# design-1v2.net
KiCad netlist of a schematic drawn in EAGLE
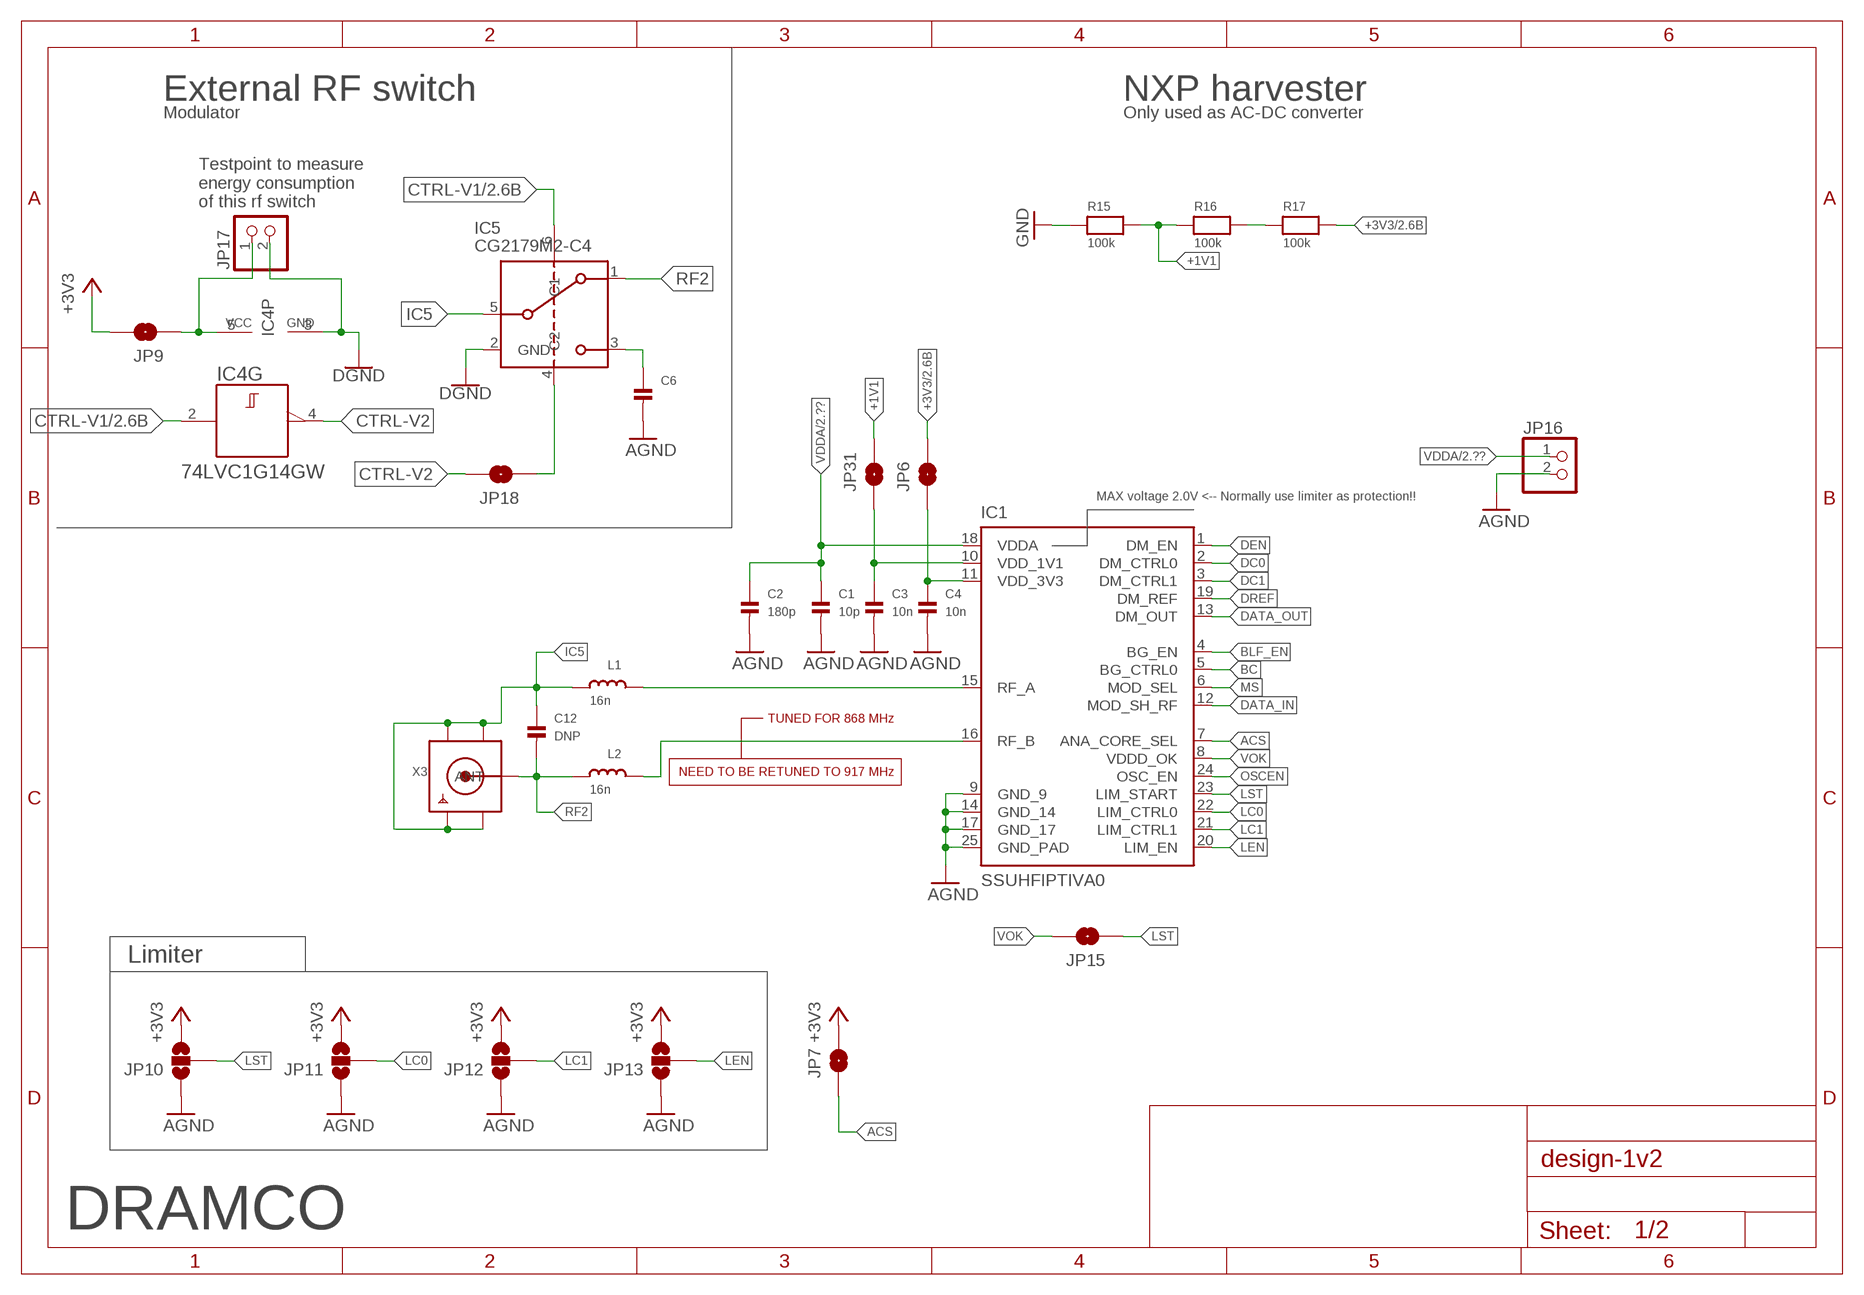
[diagram p0: schematic, sheet 1]
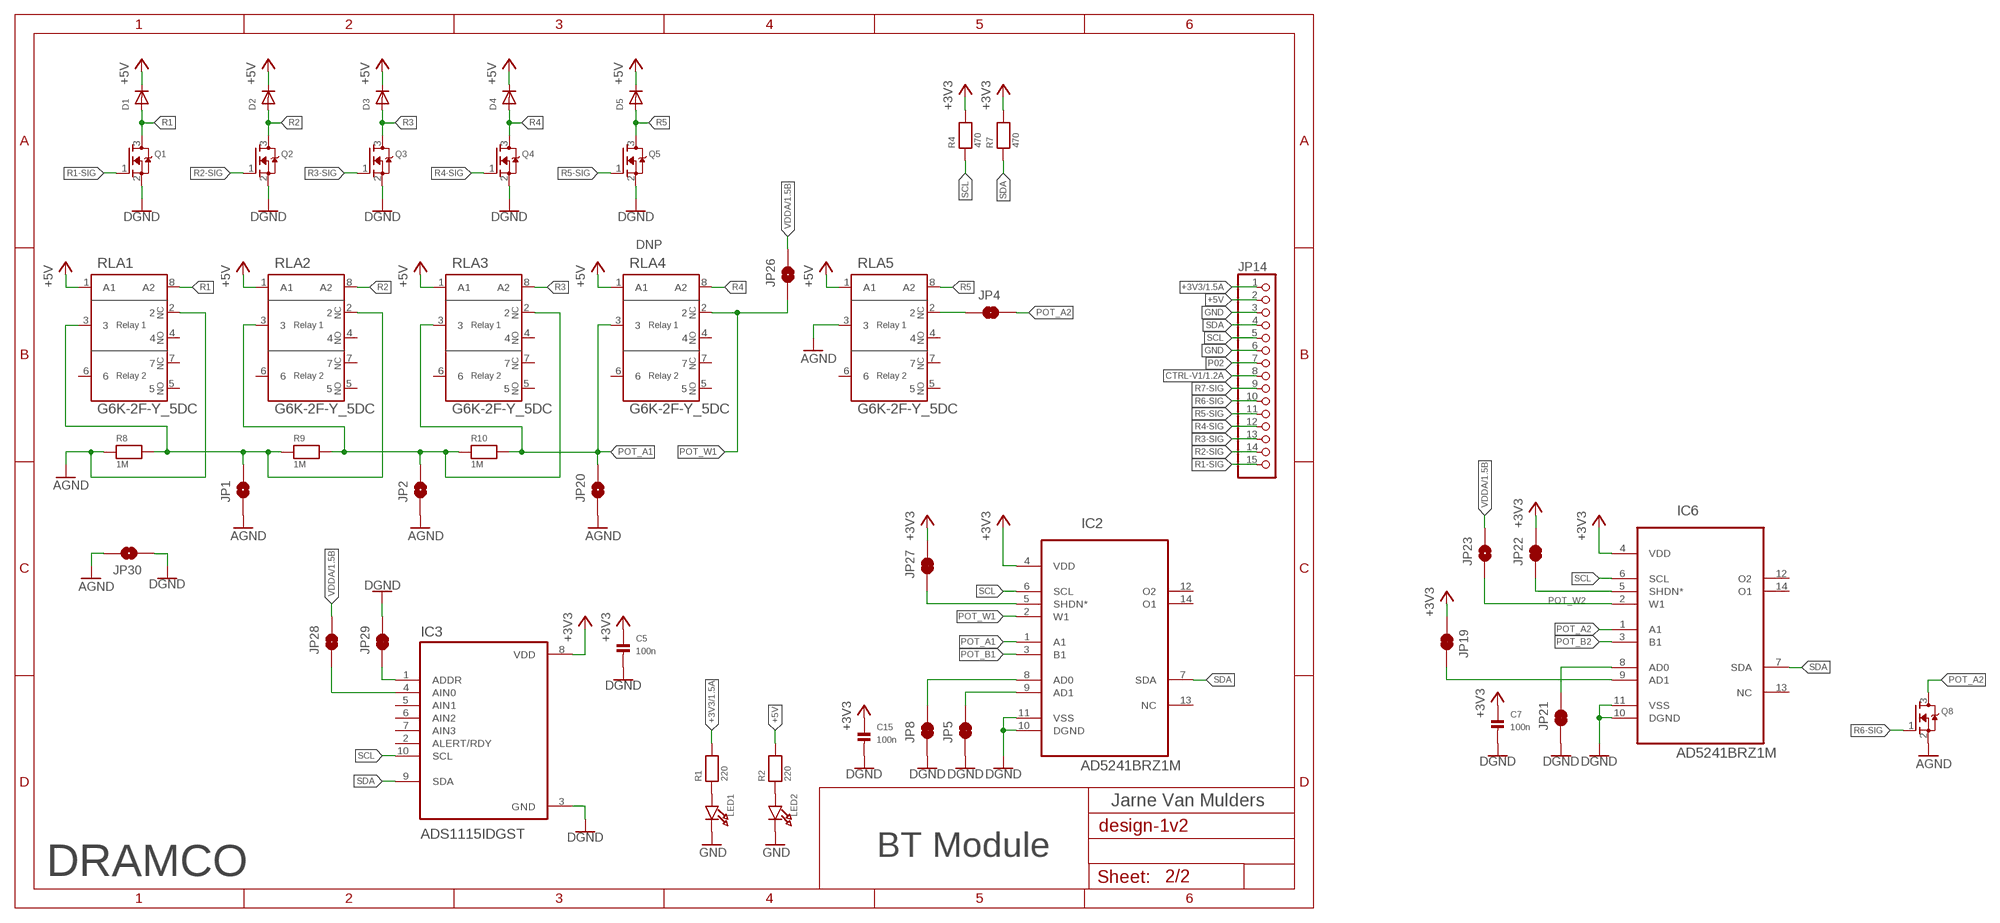
[diagram p1: schematic, sheet 2]

(export (version "E")
  (design (tool "Eeschema 10.0.6"))
  (components
    (comp (ref "C5")
      (value "100n")
      (footprint "eagle-import:0603")
      (libsource (lib "eagle-import") (part "CAP_CERAMIC0603"))
    )
    (comp (ref "C7")
      (value "100n")
      (footprint "eagle-import:0603")
      (libsource (lib "eagle-import") (part "CAP_CERAMIC0603"))
    )
    (comp (ref "C15")
      (value "100n")
      (footprint "eagle-import:0603")
      (libsource (lib "eagle-import") (part "CAP_CERAMIC0603"))
    )
    (comp (ref "D1")
      (value "DIODESOD-123")
      (footprint "eagle-import:SOD-123")
      (libsource (lib "eagle-import") (part "DIODESOD-123"))
    )
    (comp (ref "D2")
      (value "DIODESOD-123")
      (footprint "eagle-import:SOD-123")
      (libsource (lib "eagle-import") (part "DIODESOD-123"))
    )
    (comp (ref "D3")
      (value "DIODESOD-123")
      (footprint "eagle-import:SOD-123")
      (libsource (lib "eagle-import") (part "DIODESOD-123"))
    )
    (comp (ref "D4")
      (value "DIODESOD-123")
      (footprint "eagle-import:SOD-123")
      (libsource (lib "eagle-import") (part "DIODESOD-123"))
    )
    (comp (ref "D5")
      (value "DIODESOD-123")
      (footprint "eagle-import:SOD-123")
      (libsource (lib "eagle-import") (part "DIODESOD-123"))
    )
    (comp (ref "IC2")
      (value "AD5241BRZ1M")
      (footprint "eagle-import:SOIC127P600X175-14N")
      (fields (field (name "MF") "Analog Devices"))
      (libsource (lib "eagle-import") (part "AD5241BRZ1M"))
    )
    (comp (ref "IC3")
      (value "ADS1115IDGST")
      (footprint "eagle-import:SOP50P490X110-10N")
      (fields (field (name "MF") "Texas Instruments"))
      (libsource (lib "eagle-import") (part "ADS1115IDGST"))
    )
    (comp (ref "IC6")
      (value "AD5241BRZ1M")
      (footprint "eagle-import:SOIC127P600X175-14N")
      (fields (field (name "MF") "Analog Devices"))
      (libsource (lib "eagle-import") (part "AD5241BRZ1M"))
    )
    (comp (ref "JP1")
      (value "JUMPER-SMT_2_NO_NO-SILK")
      (footprint "eagle-import:SMT-JUMPER_2_NO_NO-SILK")
      (libsource (lib "eagle-import") (part "JUMPER-SMT_2_NO_NO-SILK"))
    )
    (comp (ref "JP2")
      (value "JUMPER-SMT_2_NO_NO-SILK")
      (footprint "eagle-import:SMT-JUMPER_2_NO_NO-SILK")
      (libsource (lib "eagle-import") (part "JUMPER-SMT_2_NO_NO-SILK"))
    )
    (comp (ref "JP4")
      (value "JUMPER-SMT_2_NO_NO-SILK")
      (footprint "eagle-import:SMT-JUMPER_2_NO_NO-SILK")
      (libsource (lib "eagle-import") (part "JUMPER-SMT_2_NO_NO-SILK"))
    )
    (comp (ref "JP5")
      (value "JUMPER-SMT_2_NC_TRACE_NO-SILK")
      (footprint "eagle-import:SMT-JUMPER_2_NC_TRACE_NO-SILK")
      (libsource (lib "eagle-import") (part "JUMPER-SMT_2_NC_TRACE_NO-SILK"))
    )
    (comp (ref "JP8")
      (value "JUMPER-SMT_2_NC_TRACE_NO-SILK")
      (footprint "eagle-import:SMT-JUMPER_2_NC_TRACE_NO-SILK")
      (libsource (lib "eagle-import") (part "JUMPER-SMT_2_NC_TRACE_NO-SILK"))
    )
    (comp (ref "JP14")
      (value "HEADER-1X15")
      (footprint "eagle-import:1X15_ROUND_70")
      (libsource (lib "eagle-import") (part "HEADER-1X15"))
    )
    (comp (ref "JP19")
      (value "JUMPER-SMT_2_NC_TRACE_NO-SILK")
      (footprint "eagle-import:SMT-JUMPER_2_NC_TRACE_NO-SILK")
      (libsource (lib "eagle-import") (part "JUMPER-SMT_2_NC_TRACE_NO-SILK"))
    )
    (comp (ref "JP20")
      (value "JUMPER-SMT_2_NO_NO-SILK")
      (footprint "eagle-import:SMT-JUMPER_2_NO_NO-SILK")
      (libsource (lib "eagle-import") (part "JUMPER-SMT_2_NO_NO-SILK"))
    )
    (comp (ref "JP21")
      (value "JUMPER-SMT_2_NC_TRACE_NO-SILK")
      (footprint "eagle-import:SMT-JUMPER_2_NC_TRACE_NO-SILK")
      (libsource (lib "eagle-import") (part "JUMPER-SMT_2_NC_TRACE_NO-SILK"))
    )
    (comp (ref "JP22")
      (value "JUMPER-SMT_2_NC_TRACE_NO-SILK")
      (footprint "eagle-import:SMT-JUMPER_2_NC_TRACE_NO-SILK")
      (libsource (lib "eagle-import") (part "JUMPER-SMT_2_NC_TRACE_NO-SILK"))
    )
    (comp (ref "JP23")
      (value "JUMPER-SMT_2_NO_NO-SILK")
      (footprint "eagle-import:SMT-JUMPER_2_NO_NO-SILK")
      (libsource (lib "eagle-import") (part "JUMPER-SMT_2_NO_NO-SILK"))
    )
    (comp (ref "JP26")
      (value "JUMPER-SMT_2_NO_NO-SILK")
      (footprint "eagle-import:SMT-JUMPER_2_NO_NO-SILK")
      (libsource (lib "eagle-import") (part "JUMPER-SMT_2_NO_NO-SILK"))
    )
    (comp (ref "JP27")
      (value "JUMPER-SMT_2_NC_TRACE_NO-SILK")
      (footprint "eagle-import:SMT-JUMPER_2_NC_TRACE_NO-SILK")
      (libsource (lib "eagle-import") (part "JUMPER-SMT_2_NC_TRACE_NO-SILK"))
    )
    (comp (ref "JP28")
      (value "JUMPER-SMT_2_NO_NO-SILK")
      (footprint "eagle-import:SMT-JUMPER_2_NO_NO-SILK")
      (libsource (lib "eagle-import") (part "JUMPER-SMT_2_NO_NO-SILK"))
    )
    (comp (ref "JP29")
      (value "JUMPER-SMT_2_NC_TRACE_NO-SILK")
      (footprint "eagle-import:SMT-JUMPER_2_NC_TRACE_NO-SILK")
      (libsource (lib "eagle-import") (part "JUMPER-SMT_2_NC_TRACE_NO-SILK"))
    )
    (comp (ref "JP30")
      (value "JUMPER-SMT_2_NO_NO-SILK")
      (footprint "eagle-import:SMT-JUMPER_2_NO_NO-SILK")
      (libsource (lib "eagle-import") (part "JUMPER-SMT_2_NO_NO-SILK"))
    )
    (comp (ref "LED1")
      (value "LED0805")
      (footprint "eagle-import:CHIPLED_0805")
      (libsource (lib "eagle-import") (part "LED0805"))
    )
    (comp (ref "LED2")
      (value "LED0805")
      (footprint "eagle-import:CHIPLED_0805")
      (libsource (lib "eagle-import") (part "LED0805"))
    )
    (comp (ref "Q1")
      (value "MOSFET-NREFLOW")
      (footprint "eagle-import:SOT23-R")
      (libsource (lib "eagle-import") (part "MOSFET-NREFLOW"))
    )
    (comp (ref "Q2")
      (value "MOSFET-NREFLOW")
      (footprint "eagle-import:SOT23-R")
      (libsource (lib "eagle-import") (part "MOSFET-NREFLOW"))
    )
    (comp (ref "Q3")
      (value "MOSFET-NREFLOW")
      (footprint "eagle-import:SOT23-R")
      (libsource (lib "eagle-import") (part "MOSFET-NREFLOW"))
    )
    (comp (ref "Q4")
      (value "MOSFET-NREFLOW")
      (footprint "eagle-import:SOT23-R")
      (libsource (lib "eagle-import") (part "MOSFET-NREFLOW"))
    )
    (comp (ref "Q5")
      (value "MOSFET-NREFLOW")
      (footprint "eagle-import:SOT23-R")
      (libsource (lib "eagle-import") (part "MOSFET-NREFLOW"))
    )
    (comp (ref "Q8")
      (value "MOSFET-NREFLOW")
      (footprint "eagle-import:SOT23-R")
      (libsource (lib "eagle-import") (part "MOSFET-NREFLOW"))
    )
    (comp (ref "R1")
      (value "220")
      (footprint "eagle-import:0603")
      (libsource (lib "eagle-import") (part "RESISTOR0603"))
    )
    (comp (ref "R2")
      (value "220")
      (footprint "eagle-import:0603")
      (libsource (lib "eagle-import") (part "RESISTOR0603"))
    )
    (comp (ref "R4")
      (value "470")
      (footprint "eagle-import:0603")
      (libsource (lib "eagle-import") (part "RESISTOR0603"))
    )
    (comp (ref "R7")
      (value "470")
      (footprint "eagle-import:0603")
      (libsource (lib "eagle-import") (part "RESISTOR0603"))
    )
    (comp (ref "R8")
      (value "1M")
      (footprint "eagle-import:0805")
      (libsource (lib "eagle-import") (part "RESISTOR0805"))
    )
    (comp (ref "R9")
      (value "1M")
      (footprint "eagle-import:0805")
      (libsource (lib "eagle-import") (part "RESISTOR0805"))
    )
    (comp (ref "R10")
      (value "1M")
      (footprint "eagle-import:0805")
      (libsource (lib "eagle-import") (part "RESISTOR0805"))
    )
    (comp (ref "RLA1")
      (value "G6K-2F-Y_5DC")
      (footprint "eagle-import:RELAY_G6K-2F_OMR")
      (fields
        (field (name "MANUFACTURER_PART_NUMBER") "G6K-2F-Y 5DC")
        (field (name "COPYRIGHT") "Copyright (C) 2024 Ultra Librarian. All rights reserved.")
      )
      (libsource (lib "eagle-import") (part "G6K-2F-Y_5DC"))
    )
    (comp (ref "RLA2")
      (value "G6K-2F-Y_5DC")
      (footprint "eagle-import:RELAY_G6K-2F_OMR")
      (fields
        (field (name "MANUFACTURER_PART_NUMBER") "G6K-2F-Y 5DC")
        (field (name "COPYRIGHT") "Copyright (C) 2024 Ultra Librarian. All rights reserved.")
      )
      (libsource (lib "eagle-import") (part "G6K-2F-Y_5DC"))
    )
    (comp (ref "RLA3")
      (value "G6K-2F-Y_5DC")
      (footprint "eagle-import:RELAY_G6K-2F_OMR")
      (fields
        (field (name "MANUFACTURER_PART_NUMBER") "G6K-2F-Y 5DC")
        (field (name "COPYRIGHT") "Copyright (C) 2024 Ultra Librarian. All rights reserved.")
      )
      (libsource (lib "eagle-import") (part "G6K-2F-Y_5DC"))
    )
    (comp (ref "RLA4")
      (value "G6K-2F-Y_5DC")
      (footprint "eagle-import:RELAY_G6K-2F_OMR")
      (fields
        (field (name "MANUFACTURER_PART_NUMBER") "G6K-2F-Y 5DC")
        (field (name "COPYRIGHT") "Copyright (C) 2024 Ultra Librarian. All rights reserved.")
      )
      (libsource (lib "eagle-import") (part "G6K-2F-Y_5DC"))
    )
    (comp (ref "RLA5")
      (value "G6K-2F-Y_5DC")
      (footprint "eagle-import:RELAY_G6K-2F_OMR")
      (fields
        (field (name "MANUFACTURER_PART_NUMBER") "G6K-2F-Y 5DC")
        (field (name "COPYRIGHT") "Copyright (C) 2024 Ultra Librarian. All rights reserved.")
      )
      (libsource (lib "eagle-import") (part "G6K-2F-Y_5DC"))
    )
    (comp (ref "C1")
      (value "10p")
      (footprint "eagle-import:0603")
      (libsource (lib "eagle-import") (part "CAP_CERAMIC0603"))
    )
    (comp (ref "C2")
      (value "180p")
      (footprint "eagle-import:0603")
      (libsource (lib "eagle-import") (part "CAP_CERAMIC0603"))
    )
    (comp (ref "C3")
      (value "10n")
      (footprint "eagle-import:0603")
      (libsource (lib "eagle-import") (part "CAP_CERAMIC0603"))
    )
    (comp (ref "C4")
      (value "10n")
      (footprint "eagle-import:0603")
      (libsource (lib "eagle-import") (part "CAP_CERAMIC0603"))
    )
    (comp (ref "C6")
      (value "CAP_CERAMIC0402")
      (footprint "eagle-import:0402")
      (libsource (lib "eagle-import") (part "CAP_CERAMIC0402"))
    )
    (comp (ref "C12")
      (value "DNP")
      (footprint "eagle-import:0402")
      (libsource (lib "eagle-import") (part "CAP_CERAMIC0402"))
    )
    (comp (ref "IC1")
      (value "SSUHFIPTIVA0")
      (footprint "eagle-import:QFN50P400X400X90-25N")
      (libsource (lib "eagle-import") (part "SSUHFIPTIVA0"))
    )
    (comp (ref "IC4")
      (value "74LVC1G14GW")
      (footprint "eagle-import:SOT353-1")
      (libsource (lib "eagle-import") (part "74LVC1G14GW"))
    )
    (comp (ref "IC5")
      (value "CG2179M2-C4")
      (footprint "eagle-import:SC70-6-CNC04")
      (fields (field (name "MF") "CEL"))
      (libsource (lib "eagle-import") (part "CG2179M2-C4"))
    )
    (comp (ref "JP6")
      (value "JUMPER-SMT_2_NO_NO-SILK")
      (footprint "eagle-import:SMT-JUMPER_2_NO_NO-SILK")
      (libsource (lib "eagle-import") (part "JUMPER-SMT_2_NO_NO-SILK"))
    )
    (comp (ref "JP7")
      (value "JUMPER-SMT_2_NO_NO-SILK")
      (footprint "eagle-import:SMT-JUMPER_2_NO_NO-SILK")
      (libsource (lib "eagle-import") (part "JUMPER-SMT_2_NO_NO-SILK"))
    )
    (comp (ref "JP9")
      (value "JUMPER-SMT_2_NO_NO-SILK")
      (footprint "eagle-import:SMT-JUMPER_2_NO_NO-SILK")
      (libsource (lib "eagle-import") (part "JUMPER-SMT_2_NO_NO-SILK"))
    )
    (comp (ref "JP10")
      (value "JUMPER-SMT_3_NO_SILK")
      (footprint "eagle-import:SMT-JUMPER_3_NO_SILK")
      (libsource (lib "eagle-import") (part "JUMPER-SMT_3_NO_SILK"))
    )
    (comp (ref "JP11")
      (value "JUMPER-SMT_3_NO_SILK")
      (footprint "eagle-import:SMT-JUMPER_3_NO_SILK")
      (libsource (lib "eagle-import") (part "JUMPER-SMT_3_NO_SILK"))
    )
    (comp (ref "JP12")
      (value "JUMPER-SMT_3_NO_SILK")
      (footprint "eagle-import:SMT-JUMPER_3_NO_SILK")
      (libsource (lib "eagle-import") (part "JUMPER-SMT_3_NO_SILK"))
    )
    (comp (ref "JP13")
      (value "JUMPER-SMT_3_NO_SILK")
      (footprint "eagle-import:SMT-JUMPER_3_NO_SILK")
      (libsource (lib "eagle-import") (part "JUMPER-SMT_3_NO_SILK"))
    )
    (comp (ref "JP15")
      (value "JUMPER-SMT_2_NO_NO-SILK")
      (footprint "eagle-import:SMT-JUMPER_2_NO_NO-SILK")
      (libsource (lib "eagle-import") (part "JUMPER-SMT_2_NO_NO-SILK"))
    )
    (comp (ref "JP16")
      (value "HEADER-1X2ROUND")
      (footprint "eagle-import:1X02_ROUND")
      (libsource (lib "eagle-import") (part "HEADER-1X2ROUND"))
    )
    (comp (ref "JP17")
      (value "HEADER-1X2ROUND")
      (footprint "eagle-import:1X02_ROUND")
      (libsource (lib "eagle-import") (part "HEADER-1X2ROUND"))
    )
    (comp (ref "JP18")
      (value "JUMPER-SMT_2_NO_NO-SILK")
      (footprint "eagle-import:SMT-JUMPER_2_NO_NO-SILK")
      (libsource (lib "eagle-import") (part "JUMPER-SMT_2_NO_NO-SILK"))
    )
    (comp (ref "JP31")
      (value "JUMPER-SMT_2_NO_NO-SILK")
      (footprint "eagle-import:SMT-JUMPER_2_NO_NO-SILK")
      (libsource (lib "eagle-import") (part "JUMPER-SMT_2_NO_NO-SILK"))
    )
    (comp (ref "L1")
      (value "16n")
      (footprint "eagle-import:_0402")
      (libsource (lib "eagle-import") (part "INDUCTOR_0402"))
    )
    (comp (ref "L2")
      (value "16n")
      (footprint "eagle-import:_0402")
      (libsource (lib "eagle-import") (part "INDUCTOR_0402"))
    )
    (comp (ref "R15")
      (value "100k")
      (footprint "eagle-import:0603")
      (libsource (lib "eagle-import") (part "RESISTOR0603"))
    )
    (comp (ref "R16")
      (value "100k")
      (footprint "eagle-import:0603")
      (libsource (lib "eagle-import") (part "RESISTOR0603"))
    )
    (comp (ref "R17")
      (value "100k")
      (footprint "eagle-import:0603")
      (libsource (lib "eagle-import") (part "RESISTOR0603"))
    )
    (comp (ref "X3")
      (value "SMACONNECTOR_EDGE_UFL")
      (footprint "eagle-import:SMA_EDGELAUNCH_UFL")
      (libsource (lib "eagle-import") (part "SMACONNECTOR_EDGE_UFL"))
    )
  )
  (nets
    (net (code "1") (name "+1V1") (class "Default")
      (node (ref "JP31") (pin "2") (pinfunction "2_2") (pintype "passive"))
      (node (ref "R15") (pin "2") (pinfunction "2_2") (pintype "passive"))
      (node (ref "R16") (pin "1") (pinfunction "1_1") (pintype "passive"))
    )
    (net (code "2") (name "+3V3") (class "Default")
      (node (ref "C15") (pin "1") (pinfunction "P$1_1") (pintype "passive"))
      (node (ref "C5") (pin "1") (pinfunction "P$1_1") (pintype "passive"))
      (node (ref "C7") (pin "1") (pinfunction "P$1_1") (pintype "passive"))
      (node (ref "IC2") (pin "4") (pinfunction "VDD_4") (pintype "power_in"))
      (node (ref "IC3") (pin "8") (pinfunction "VDD_8") (pintype "power_in"))
      (node (ref "IC6") (pin "4") (pinfunction "VDD_4") (pintype "power_in"))
      (node (ref "JP10") (pin "3") (pinfunction "3_3") (pintype "passive"))
      (node (ref "JP11") (pin "3") (pinfunction "3_3") (pintype "passive"))
      (node (ref "JP12") (pin "3") (pinfunction "3_3") (pintype "passive"))
      (node (ref "JP13") (pin "3") (pinfunction "3_3") (pintype "passive"))
      (node (ref "JP14") (pin "1") (pinfunction "1_1") (pintype "passive"))
      (node (ref "JP19") (pin "1") (pinfunction "1_1") (pintype "passive"))
      (node (ref "JP22") (pin "2") (pinfunction "2_2") (pintype "passive"))
      (node (ref "JP27") (pin "2") (pinfunction "2_2") (pintype "passive"))
      (node (ref "JP6") (pin "2") (pinfunction "2_2") (pintype "passive"))
      (node (ref "JP7") (pin "2") (pinfunction "2_2") (pintype "passive"))
      (node (ref "JP9") (pin "2") (pinfunction "2_2") (pintype "passive"))
      (node (ref "R1") (pin "2") (pinfunction "2_2") (pintype "passive"))
      (node (ref "R17") (pin "2") (pinfunction "2_2") (pintype "passive"))
      (node (ref "R4") (pin "2") (pinfunction "2_2") (pintype "passive"))
      (node (ref "R7") (pin "2") (pinfunction "2_2") (pintype "passive"))
    )
    (net (code "3") (name "+5V") (class "Default")
      (node (ref "D1") (pin "C") (pinfunction "C_C") (pintype "passive"))
      (node (ref "D2") (pin "C") (pinfunction "C_C") (pintype "passive"))
      (node (ref "D3") (pin "C") (pinfunction "C_C") (pintype "passive"))
      (node (ref "D4") (pin "C") (pinfunction "C_C") (pintype "passive"))
      (node (ref "D5") (pin "C") (pinfunction "C_C") (pintype "passive"))
      (node (ref "JP14") (pin "2") (pinfunction "2_2") (pintype "passive"))
      (node (ref "R2") (pin "2") (pinfunction "2_2") (pintype "passive"))
      (node (ref "RLA1") (pin "1") (pinfunction "A1_1") (pintype "passive"))
      (node (ref "RLA2") (pin "1") (pinfunction "A1_1") (pintype "passive"))
      (node (ref "RLA3") (pin "1") (pinfunction "A1_1") (pintype "passive"))
      (node (ref "RLA4") (pin "1") (pinfunction "A1_1") (pintype "passive"))
      (node (ref "RLA5") (pin "1") (pinfunction "A1_1") (pintype "passive"))
    )
    (net (code "4") (name "ACS") (class "Default")
      (node (ref "IC1") (pin "7") (pinfunction "ANA_CORE_SEL_7") (pintype "bidirectional"))
      (node (ref "JP7") (pin "1") (pinfunction "1_1") (pintype "passive"))
    )
    (net (code "5") (name "AGND") (class "Default")
      (node (ref "C1") (pin "2") (pinfunction "P$2_2") (pintype "passive"))
      (node (ref "C2") (pin "2") (pinfunction "P$2_2") (pintype "passive"))
      (node (ref "C3") (pin "2") (pinfunction "P$2_2") (pintype "passive"))
      (node (ref "C4") (pin "2") (pinfunction "P$2_2") (pintype "passive"))
      (node (ref "C6") (pin "2") (pinfunction "P$2_2") (pintype "passive"))
      (node (ref "IC1") (pin "14") (pinfunction "GND_14_14") (pintype "bidirectional"))
      (node (ref "IC1") (pin "17") (pinfunction "GND_17_17") (pintype "bidirectional"))
      (node (ref "IC1") (pin "25") (pinfunction "GND_PAD_25") (pintype "bidirectional"))
      (node (ref "IC1") (pin "9") (pinfunction "GND_9_9") (pintype "bidirectional"))
      (node (ref "JP1") (pin "1") (pinfunction "1_1") (pintype "passive"))
      (node (ref "JP10") (pin "1") (pinfunction "1_1") (pintype "passive"))
      (node (ref "JP11") (pin "1") (pinfunction "1_1") (pintype "passive"))
      (node (ref "JP12") (pin "1") (pinfunction "1_1") (pintype "passive"))
      (node (ref "JP13") (pin "1") (pinfunction "1_1") (pintype "passive"))
      (node (ref "JP16") (pin "2") (pinfunction "2_2") (pintype "passive"))
      (node (ref "JP2") (pin "1") (pinfunction "1_1") (pintype "passive"))
      (node (ref "JP20") (pin "1") (pinfunction "1_1") (pintype "passive"))
      (node (ref "JP30") (pin "2") (pinfunction "2_2") (pintype "passive"))
      (node (ref "Q8") (pin "2") (pinfunction "S_2") (pintype "bidirectional"))
      (node (ref "R8") (pin "1") (pinfunction "1_1") (pintype "passive"))
      (node (ref "RLA1") (pin "2") (pinfunction "2_2") (pintype "passive"))
      (node (ref "RLA5") (pin "3") (pinfunction "3_3") (pintype "passive"))
    )
    (net (code "6") (name "BC") (class "Default")
      (node (ref "IC1") (pin "5") (pinfunction "BG_CTRL0_5") (pintype "bidirectional"))
    )
    (net (code "7") (name "BLF_EN") (class "Default")
      (node (ref "IC1") (pin "4") (pinfunction "BG_EN_4") (pintype "bidirectional"))
    )
    (net (code "8") (name "CTRL-V1") (class "Default")
      (node (ref "IC4") (pin "2") (pinfunction "A_2") (pintype "input"))
      (node (ref "IC5") (pin "6") (pinfunction "C1_6") (pintype "bidirectional"))
      (node (ref "JP14") (pin "8") (pinfunction "8_8") (pintype "passive"))
    )
    (net (code "9") (name "CTRL-V2") (class "Default")
      (node (ref "IC4") (pin "4") (pinfunction "Y_4") (pintype "output"))
      (node (ref "JP18") (pin "2") (pinfunction "2_2") (pintype "passive"))
    )
    (net (code "10") (name "DATA_IN") (class "Default")
      (node (ref "IC1") (pin "12") (pinfunction "MOD_SH_RF_12") (pintype "bidirectional"))
    )
    (net (code "11") (name "DATA_OUT") (class "Default")
      (node (ref "IC1") (pin "13") (pinfunction "DM_OUT_13") (pintype "bidirectional"))
    )
    (net (code "12") (name "DC0") (class "Default")
      (node (ref "IC1") (pin "2") (pinfunction "DM_CTRL0_2") (pintype "bidirectional"))
    )
    (net (code "13") (name "DC1") (class "Default")
      (node (ref "IC1") (pin "3") (pinfunction "DM_CTRL1_3") (pintype "bidirectional"))
    )
    (net (code "14") (name "DEN") (class "Default")
      (node (ref "IC1") (pin "1") (pinfunction "DM_EN_1") (pintype "bidirectional"))
    )
    (net (code "15") (name "DREF") (class "Default")
      (node (ref "IC1") (pin "19") (pinfunction "DM_REF_19") (pintype "bidirectional"))
    )
    (net (code "16") (name "GND") (class "Default")
      (node (ref "C15") (pin "2") (pinfunction "P$2_2") (pintype "passive"))
      (node (ref "C5") (pin "2") (pinfunction "P$2_2") (pintype "passive"))
      (node (ref "C7") (pin "2") (pinfunction "P$2_2") (pintype "passive"))
      (node (ref "IC2") (pin "10") (pinfunction "DGND_10") (pintype "passive"))
      (node (ref "IC2") (pin "11") (pinfunction "VSS_11") (pintype "power_in"))
      (node (ref "IC3") (pin "3") (pinfunction "GND_3") (pintype "power_in"))
      (node (ref "IC4") (pin "3") (pinfunction "GND_3") (pintype "power_in"))
      (node (ref "IC5") (pin "2") (pinfunction "GND_2") (pintype "bidirectional"))
      (node (ref "IC6") (pin "10") (pinfunction "DGND_10") (pintype "passive"))
      (node (ref "IC6") (pin "11") (pinfunction "VSS_11") (pintype "power_in"))
      (node (ref "JP14") (pin "3") (pinfunction "3_3") (pintype "passive"))
      (node (ref "JP14") (pin "6") (pinfunction "6_6") (pintype "passive"))
      (node (ref "JP17") (pin "2") (pinfunction "2_2") (pintype "passive"))
      (node (ref "JP21") (pin "1") (pinfunction "1_1") (pintype "passive"))
      (node (ref "JP29") (pin "2") (pinfunction "2_2") (pintype "passive"))
      (node (ref "JP30") (pin "1") (pinfunction "1_1") (pintype "passive"))
      (node (ref "JP5") (pin "1") (pinfunction "1_1") (pintype "passive"))
      (node (ref "JP8") (pin "1") (pinfunction "1_1") (pintype "passive"))
      (node (ref "LED1") (pin "C") (pinfunction "C_C") (pintype "passive"))
      (node (ref "LED2") (pin "C") (pinfunction "C_C") (pintype "passive"))
      (node (ref "Q1") (pin "2") (pinfunction "S_2") (pintype "bidirectional"))
      (node (ref "Q2") (pin "2") (pinfunction "S_2") (pintype "bidirectional"))
      (node (ref "Q3") (pin "2") (pinfunction "S_2") (pintype "bidirectional"))
      (node (ref "Q4") (pin "2") (pinfunction "S_2") (pintype "bidirectional"))
      (node (ref "Q5") (pin "2") (pinfunction "S_2") (pintype "bidirectional"))
      (node (ref "R15") (pin "1") (pinfunction "1_1") (pintype "passive"))
    )
    (net (code "17") (name "IC5") (class "Default")
      (node (ref "C12") (pin "1") (pinfunction "P$1_1") (pintype "passive"))
      (node (ref "IC5") (pin "5") (pinfunction "PC_5") (pintype "bidirectional"))
      (node (ref "L1") (pin "1") (pinfunction "1_1") (pintype "passive"))
      (node (ref "X3") (pin "GND@1") (pinfunction "GND1_GND@1") (pintype "power_in"))
      (node (ref "X3") (pin "GND@2") (pinfunction "GND2_GND@2") (pintype "power_in"))
      (node (ref "X3") (pin "GND@3") (pinfunction "GND3_GND@3") (pintype "power_in"))
      (node (ref "X3") (pin "GND@4") (pinfunction "GND4_GND@4") (pintype "power_in"))
    )
    (net (code "18") (name "LC0") (class "Default")
      (node (ref "IC1") (pin "22") (pinfunction "LIM_CTRL0_22") (pintype "bidirectional"))
      (node (ref "JP11") (pin "2") (pinfunction "2_2") (pintype "passive"))
    )
    (net (code "19") (name "LC1") (class "Default")
      (node (ref "IC1") (pin "21") (pinfunction "LIM_CTRL1_21") (pintype "bidirectional"))
      (node (ref "JP12") (pin "2") (pinfunction "2_2") (pintype "passive"))
    )
    (net (code "20") (name "LEN") (class "Default")
      (node (ref "IC1") (pin "20") (pinfunction "LIM_EN_20") (pintype "bidirectional"))
      (node (ref "JP13") (pin "2") (pinfunction "2_2") (pintype "passive"))
    )
    (net (code "21") (name "LST") (class "Default")
      (node (ref "IC1") (pin "23") (pinfunction "LIM_START_23") (pintype "bidirectional"))
      (node (ref "JP10") (pin "2") (pinfunction "2_2") (pintype "passive"))
      (node (ref "JP15") (pin "1") (pinfunction "1_1") (pintype "passive"))
    )
    (net (code "22") (name "MS") (class "Default")
      (node (ref "IC1") (pin "6") (pinfunction "MOD_SEL_6") (pintype "bidirectional"))
    )
    (net (code "23") (name "Net-(C3-P$1)") (class "Default")
      (node (ref "C3") (pin "1") (pinfunction "P$1_1") (pintype "passive"))
      (node (ref "IC1") (pin "10") (pinfunction "VDD_1V1_10") (pintype "bidirectional"))
      (node (ref "JP31") (pin "1") (pinfunction "1_1") (pintype "passive"))
    )
    (net (code "24") (name "Net-(C4-P$1)") (class "Default")
      (node (ref "C4") (pin "1") (pinfunction "P$1_1") (pintype "passive"))
      (node (ref "IC1") (pin "11") (pinfunction "VDD_3V3_11") (pintype "bidirectional"))
      (node (ref "JP6") (pin "1") (pinfunction "1_1") (pintype "passive"))
    )
    (net (code "25") (name "Net-(C6-P$1)") (class "Default")
      (node (ref "C6") (pin "1") (pinfunction "P$1_1") (pintype "passive"))
      (node (ref "IC5") (pin "3") (pinfunction "P2_3") (pintype "bidirectional"))
    )
    (net (code "26") (name "Net-(IC1-RF_A)") (class "Default")
      (node (ref "IC1") (pin "15") (pinfunction "RF_A_15") (pintype "bidirectional"))
      (node (ref "L1") (pin "2") (pinfunction "2_2") (pintype "passive"))
    )
    (net (code "27") (name "Net-(IC1-RF_B)") (class "Default")
      (node (ref "IC1") (pin "16") (pinfunction "RF_B_16") (pintype "bidirectional"))
      (node (ref "L2") (pin "2") (pinfunction "2_2") (pintype "passive"))
    )
    (net (code "28") (name "Net-(IC2-AD0)") (class "Default")
      (node (ref "IC2") (pin "8") (pinfunction "AD0_8") (pintype "passive"))
      (node (ref "JP8") (pin "2") (pinfunction "2_2") (pintype "passive"))
    )
    (net (code "29") (name "Net-(IC2-AD1)") (class "Default")
      (node (ref "IC2") (pin "9") (pinfunction "AD1_9") (pintype "passive"))
      (node (ref "JP5") (pin "2") (pinfunction "2_2") (pintype "passive"))
    )
    (net (code "30") (name "Net-(IC2-SHDN*)") (class "Default")
      (node (ref "IC2") (pin "5") (pinfunction "SHDN*_5") (pintype "passive"))
      (node (ref "JP27") (pin "1") (pinfunction "1_1") (pintype "passive"))
    )
    (net (code "31") (name "Net-(IC3-ADDR)") (class "Default")
      (node (ref "IC3") (pin "1") (pinfunction "ADDR_1") (pintype "input"))
      (node (ref "JP29") (pin "1") (pinfunction "1_1") (pintype "passive"))
    )
    (net (code "32") (name "Net-(IC3-AIN0)") (class "Default")
      (node (ref "IC3") (pin "4") (pinfunction "AIN0_4") (pintype "input"))
      (node (ref "JP28") (pin "1") (pinfunction "1_1") (pintype "passive"))
    )
    (net (code "33") (name "Net-(IC4B-VCC)") (class "Default")
      (node (ref "IC4") (pin "5") (pinfunction "VCC_5") (pintype "power_in"))
      (node (ref "JP17") (pin "1") (pinfunction "1_1") (pintype "passive"))
      (node (ref "JP9") (pin "1") (pinfunction "1_1") (pintype "passive"))
    )
    (net (code "34") (name "Net-(IC5-C2)") (class "Default")
      (node (ref "IC5") (pin "4") (pinfunction "C2_4") (pintype "bidirectional"))
      (node (ref "JP18") (pin "1") (pinfunction "1_1") (pintype "passive"))
    )
    (net (code "35") (name "Net-(IC6-AD0)") (class "Default")
      (node (ref "IC6") (pin "8") (pinfunction "AD0_8") (pintype "passive"))
      (node (ref "JP21") (pin "2") (pinfunction "2_2") (pintype "passive"))
    )
    (net (code "36") (name "Net-(IC6-AD1)") (class "Default")
      (node (ref "IC6") (pin "9") (pinfunction "AD1_9") (pintype "passive"))
      (node (ref "JP19") (pin "2") (pinfunction "2_2") (pintype "passive"))
    )
    (net (code "37") (name "Net-(IC6-SHDN*)") (class "Default")
      (node (ref "IC6") (pin "5") (pinfunction "SHDN*_5") (pintype "passive"))
      (node (ref "JP22") (pin "1") (pinfunction "1_1") (pintype "passive"))
    )
    (net (code "38") (name "Net-(JP1-Pad2)") (class "Default")
      (node (ref "JP1") (pin "2") (pinfunction "2_2") (pintype "passive"))
      (node (ref "R8") (pin "2") (pinfunction "2_2") (pintype "passive"))
      (node (ref "R9") (pin "1") (pinfunction "1_1") (pintype "passive"))
      (node (ref "RLA1") (pin "3") (pinfunction "3_3") (pintype "passive"))
      (node (ref "RLA2") (pin "2") (pinfunction "2_2") (pintype "passive"))
    )
    (net (code "39") (name "Net-(JP2-Pad2)") (class "Default")
      (node (ref "JP2") (pin "2") (pinfunction "2_2") (pintype "passive"))
      (node (ref "R10") (pin "1") (pinfunction "1_1") (pintype "passive"))
      (node (ref "R9") (pin "2") (pinfunction "2_2") (pintype "passive"))
      (node (ref "RLA2") (pin "3") (pinfunction "3_3") (pintype "passive"))
      (node (ref "RLA3") (pin "2") (pinfunction "2_2") (pintype "passive"))
    )
    (net (code "40") (name "Net-(JP4-Pad1)") (class "Default")
      (node (ref "JP4") (pin "1") (pinfunction "1_1") (pintype "passive"))
      (node (ref "RLA5") (pin "2") (pinfunction "2_2") (pintype "passive"))
    )
    (net (code "41") (name "Net-(LED1-PadA)") (class "Default")
      (node (ref "LED1") (pin "A") (pinfunction "A_A") (pintype "passive"))
      (node (ref "R1") (pin "1") (pinfunction "1_1") (pintype "passive"))
    )
    (net (code "42") (name "Net-(LED2-PadA)") (class "Default")
      (node (ref "LED2") (pin "A") (pinfunction "A_A") (pintype "passive"))
      (node (ref "R2") (pin "1") (pinfunction "1_1") (pintype "passive"))
    )
    (net (code "43") (name "Net-(R16-Pad2)") (class "Default")
      (node (ref "R16") (pin "2") (pinfunction "2_2") (pintype "passive"))
      (node (ref "R17") (pin "1") (pinfunction "1_1") (pintype "passive"))
    )
    (net (code "44") (name "OSCEN") (class "Default")
      (node (ref "IC1") (pin "24") (pinfunction "OSC_EN_24") (pintype "bidirectional"))
    )
    (net (code "45") (name "P02") (class "Default")
      (node (ref "JP14") (pin "7") (pinfunction "7_7") (pintype "passive"))
    )
    (net (code "46") (name "POT_A1") (class "Default")
      (node (ref "IC2") (pin "1") (pinfunction "A1_1") (pintype "passive"))
      (node (ref "JP20") (pin "2") (pinfunction "2_2") (pintype "passive"))
      (node (ref "R10") (pin "2") (pinfunction "2_2") (pintype "passive"))
      (node (ref "RLA3") (pin "3") (pinfunction "3_3") (pintype "passive"))
      (node (ref "RLA4") (pin "3") (pinfunction "3_3") (pintype "passive"))
    )
    (net (code "47") (name "POT_A2") (class "Default")
      (node (ref "IC6") (pin "1") (pinfunction "A1_1") (pintype "passive"))
      (node (ref "JP4") (pin "2") (pinfunction "2_2") (pintype "passive"))
      (node (ref "Q8") (pin "3") (pinfunction "D_3") (pintype "bidirectional"))
    )
    (net (code "48") (name "POT_B1") (class "Default")
      (node (ref "IC2") (pin "3") (pinfunction "B1_3") (pintype "passive"))
    )
    (net (code "49") (name "POT_B2") (class "Default")
      (node (ref "IC6") (pin "3") (pinfunction "B1_3") (pintype "passive"))
    )
    (net (code "50") (name "POT_W1") (class "Default")
      (node (ref "IC2") (pin "2") (pinfunction "W1_2") (pintype "passive"))
      (node (ref "JP26") (pin "1") (pinfunction "1_1") (pintype "passive"))
      (node (ref "RLA4") (pin "2") (pinfunction "2_2") (pintype "passive"))
    )
    (net (code "51") (name "POT_W2") (class "Default")
      (node (ref "IC6") (pin "2") (pinfunction "W1_2") (pintype "passive"))
      (node (ref "JP23") (pin "1") (pinfunction "1_1") (pintype "passive"))
    )
    (net (code "52") (name "R1") (class "Default")
      (node (ref "D1") (pin "A") (pinfunction "A_A") (pintype "passive"))
      (node (ref "Q1") (pin "3") (pinfunction "D_3") (pintype "bidirectional"))
      (node (ref "RLA1") (pin "8") (pinfunction "A2_8") (pintype "passive"))
    )
    (net (code "53") (name "R1-SIG") (class "Default")
      (node (ref "JP14") (pin "15") (pinfunction "15_15") (pintype "passive"))
      (node (ref "Q1") (pin "1") (pinfunction "G_1") (pintype "bidirectional"))
    )
    (net (code "54") (name "R2") (class "Default")
      (node (ref "D2") (pin "A") (pinfunction "A_A") (pintype "passive"))
      (node (ref "Q2") (pin "3") (pinfunction "D_3") (pintype "bidirectional"))
      (node (ref "RLA2") (pin "8") (pinfunction "A2_8") (pintype "passive"))
    )
    (net (code "55") (name "R2-SIG") (class "Default")
      (node (ref "JP14") (pin "14") (pinfunction "14_14") (pintype "passive"))
      (node (ref "Q2") (pin "1") (pinfunction "G_1") (pintype "bidirectional"))
    )
    (net (code "56") (name "R3") (class "Default")
      (node (ref "D3") (pin "A") (pinfunction "A_A") (pintype "passive"))
      (node (ref "Q3") (pin "3") (pinfunction "D_3") (pintype "bidirectional"))
      (node (ref "RLA3") (pin "8") (pinfunction "A2_8") (pintype "passive"))
    )
    (net (code "57") (name "R3-SIG") (class "Default")
      (node (ref "JP14") (pin "13") (pinfunction "13_13") (pintype "passive"))
      (node (ref "Q3") (pin "1") (pinfunction "G_1") (pintype "bidirectional"))
    )
    (net (code "58") (name "R4") (class "Default")
      (node (ref "D4") (pin "A") (pinfunction "A_A") (pintype "passive"))
      (node (ref "Q4") (pin "3") (pinfunction "D_3") (pintype "bidirectional"))
      (node (ref "RLA4") (pin "8") (pinfunction "A2_8") (pintype "passive"))
    )
    (net (code "59") (name "R4-SIG") (class "Default")
      (node (ref "JP14") (pin "12") (pinfunction "12_12") (pintype "passive"))
      (node (ref "Q4") (pin "1") (pinfunction "G_1") (pintype "bidirectional"))
    )
    (net (code "60") (name "R5") (class "Default")
      (node (ref "D5") (pin "A") (pinfunction "A_A") (pintype "passive"))
      (node (ref "Q5") (pin "3") (pinfunction "D_3") (pintype "bidirectional"))
      (node (ref "RLA5") (pin "8") (pinfunction "A2_8") (pintype "passive"))
    )
    (net (code "61") (name "R5-SIG") (class "Default")
      (node (ref "JP14") (pin "11") (pinfunction "11_11") (pintype "passive"))
      (node (ref "Q5") (pin "1") (pinfunction "G_1") (pintype "bidirectional"))
    )
    (net (code "62") (name "R6-SIG") (class "Default")
      (node (ref "JP14") (pin "10") (pinfunction "10_10") (pintype "passive"))
      (node (ref "Q8") (pin "1") (pinfunction "G_1") (pintype "bidirectional"))
    )
    (net (code "63") (name "R7-SIG") (class "Default")
      (node (ref "JP14") (pin "9") (pinfunction "9_9") (pintype "passive"))
    )
    (net (code "64") (name "RF2") (class "Default")
      (node (ref "C12") (pin "2") (pinfunction "P$2_2") (pintype "passive"))
      (node (ref "IC5") (pin "1") (pinfunction "P1_1") (pintype "bidirectional"))
      (node (ref "L2") (pin "1") (pinfunction "1_1") (pintype "passive"))
      (node (ref "X3") (pin "P") (pinfunction "ANT_P") (pintype "bidirectional"))
    )
    (net (code "65") (name "SCL") (class "Default")
      (node (ref "IC2") (pin "6") (pinfunction "SCL_6") (pintype "passive"))
      (node (ref "IC3") (pin "10") (pinfunction "SCL_10") (pintype "input"))
      (node (ref "IC6") (pin "6") (pinfunction "SCL_6") (pintype "passive"))
      (node (ref "JP14") (pin "5") (pinfunction "5_5") (pintype "passive"))
      (node (ref "R4") (pin "1") (pinfunction "1_1") (pintype "passive"))
    )
    (net (code "66") (name "SDA") (class "Default")
      (node (ref "IC2") (pin "7") (pinfunction "SDA_7") (pintype "passive"))
      (node (ref "IC3") (pin "9") (pinfunction "SDA_9") (pintype "bidirectional"))
      (node (ref "IC6") (pin "7") (pinfunction "SDA_7") (pintype "passive"))
      (node (ref "JP14") (pin "4") (pinfunction "4_4") (pintype "passive"))
      (node (ref "R7") (pin "1") (pinfunction "1_1") (pintype "passive"))
    )
    (net (code "67") (name "VDDA") (class "Default")
      (node (ref "C1") (pin "1") (pinfunction "P$1_1") (pintype "passive"))
      (node (ref "C2") (pin "1") (pinfunction "P$1_1") (pintype "passive"))
      (node (ref "IC1") (pin "18") (pinfunction "VDDA_18") (pintype "bidirectional"))
      (node (ref "JP16") (pin "1") (pinfunction "1_1") (pintype "passive"))
      (node (ref "JP23") (pin "2") (pinfunction "2_2") (pintype "passive"))
      (node (ref "JP26") (pin "2") (pinfunction "2_2") (pintype "passive"))
      (node (ref "JP28") (pin "2") (pinfunction "2_2") (pintype "passive"))
    )
    (net (code "68") (name "VOK") (class "Default")
      (node (ref "IC1") (pin "8") (pinfunction "VDDD_OK_8") (pintype "bidirectional"))
      (node (ref "JP15") (pin "2") (pinfunction "2_2") (pintype "passive"))
    )
    (net (code "69") (name "unconnected-(IC2-NC-Pad13)") (class "Default")
      (node (ref "IC2") (pin "13") (pinfunction "NC_13") (pintype "passive"))
    )
    (net (code "70") (name "unconnected-(IC2-O1-Pad14)") (class "Default")
      (node (ref "IC2") (pin "14") (pinfunction "O1_14") (pintype "passive"))
    )
    (net (code "71") (name "unconnected-(IC2-O2-Pad12)") (class "Default")
      (node (ref "IC2") (pin "12") (pinfunction "O2_12") (pintype "passive"))
    )
    (net (code "72") (name "unconnected-(IC3-AIN1-Pad5)") (class "Default")
      (node (ref "IC3") (pin "5") (pinfunction "AIN1_5") (pintype "input"))
    )
    (net (code "73") (name "unconnected-(IC3-AIN2-Pad6)") (class "Default")
      (node (ref "IC3") (pin "6") (pinfunction "AIN2_6") (pintype "input"))
    )
    (net (code "74") (name "unconnected-(IC3-AIN3-Pad7)") (class "Default")
      (node (ref "IC3") (pin "7") (pinfunction "AIN3_7") (pintype "input"))
    )
    (net (code "75") (name "unconnected-(IC3-ALERT{slash}RDY-Pad2)") (class "Default")
      (node (ref "IC3") (pin "2") (pinfunction "ALERT/RDY_2") (pintype "input"))
    )
    (net (code "76") (name "unconnected-(IC6-NC-Pad13)") (class "Default")
      (node (ref "IC6") (pin "13") (pinfunction "NC_13") (pintype "passive"))
    )
    (net (code "77") (name "unconnected-(IC6-O1-Pad14)") (class "Default")
      (node (ref "IC6") (pin "14") (pinfunction "O1_14") (pintype "passive"))
    )
    (net (code "78") (name "unconnected-(IC6-O2-Pad12)") (class "Default")
      (node (ref "IC6") (pin "12") (pinfunction "O2_12") (pintype "passive"))
    )
    (net (code "79") (name "unconnected-(RLA1-Pad4)") (class "Default")
      (node (ref "RLA1") (pin "4") (pinfunction "4_4") (pintype "passive"))
    )
    (net (code "80") (name "unconnected-(RLA1-Pad5)") (class "Default")
      (node (ref "RLA1") (pin "5") (pinfunction "5_5") (pintype "passive"))
    )
    (net (code "81") (name "unconnected-(RLA1-Pad6)") (class "Default")
      (node (ref "RLA1") (pin "6") (pinfunction "6_6") (pintype "passive"))
    )
    (net (code "82") (name "unconnected-(RLA1-Pad7)") (class "Default")
      (node (ref "RLA1") (pin "7") (pinfunction "7_7") (pintype "passive"))
    )
    (net (code "83") (name "unconnected-(RLA2-Pad4)") (class "Default")
      (node (ref "RLA2") (pin "4") (pinfunction "4_4") (pintype "passive"))
    )
    (net (code "84") (name "unconnected-(RLA2-Pad5)") (class "Default")
      (node (ref "RLA2") (pin "5") (pinfunction "5_5") (pintype "passive"))
    )
    (net (code "85") (name "unconnected-(RLA2-Pad6)") (class "Default")
      (node (ref "RLA2") (pin "6") (pinfunction "6_6") (pintype "passive"))
    )
    (net (code "86") (name "unconnected-(RLA2-Pad7)") (class "Default")
      (node (ref "RLA2") (pin "7") (pinfunction "7_7") (pintype "passive"))
    )
    (net (code "87") (name "unconnected-(RLA3-Pad4)") (class "Default")
      (node (ref "RLA3") (pin "4") (pinfunction "4_4") (pintype "passive"))
    )
    (net (code "88") (name "unconnected-(RLA3-Pad5)") (class "Default")
      (node (ref "RLA3") (pin "5") (pinfunction "5_5") (pintype "passive"))
    )
    (net (code "89") (name "unconnected-(RLA3-Pad6)") (class "Default")
      (node (ref "RLA3") (pin "6") (pinfunction "6_6") (pintype "passive"))
    )
    (net (code "90") (name "unconnected-(RLA3-Pad7)") (class "Default")
      (node (ref "RLA3") (pin "7") (pinfunction "7_7") (pintype "passive"))
    )
    (net (code "91") (name "unconnected-(RLA4-Pad4)") (class "Default")
      (node (ref "RLA4") (pin "4") (pinfunction "4_4") (pintype "passive"))
    )
    (net (code "92") (name "unconnected-(RLA4-Pad5)") (class "Default")
      (node (ref "RLA4") (pin "5") (pinfunction "5_5") (pintype "passive"))
    )
    (net (code "93") (name "unconnected-(RLA4-Pad6)") (class "Default")
      (node (ref "RLA4") (pin "6") (pinfunction "6_6") (pintype "passive"))
    )
    (net (code "94") (name "unconnected-(RLA4-Pad7)") (class "Default")
      (node (ref "RLA4") (pin "7") (pinfunction "7_7") (pintype "passive"))
    )
    (net (code "95") (name "unconnected-(RLA5-Pad4)") (class "Default")
      (node (ref "RLA5") (pin "4") (pinfunction "4_4") (pintype "passive"))
    )
    (net (code "96") (name "unconnected-(RLA5-Pad5)") (class "Default")
      (node (ref "RLA5") (pin "5") (pinfunction "5_5") (pintype "passive"))
    )
    (net (code "97") (name "unconnected-(RLA5-Pad6)") (class "Default")
      (node (ref "RLA5") (pin "6") (pinfunction "6_6") (pintype "passive"))
    )
    (net (code "98") (name "unconnected-(RLA5-Pad7)") (class "Default")
      (node (ref "RLA5") (pin "7") (pinfunction "7_7") (pintype "passive"))
    )
  )
)
